# CH32V002F4P.net
KiCad netlist of a schematic drawn in Altium Designer
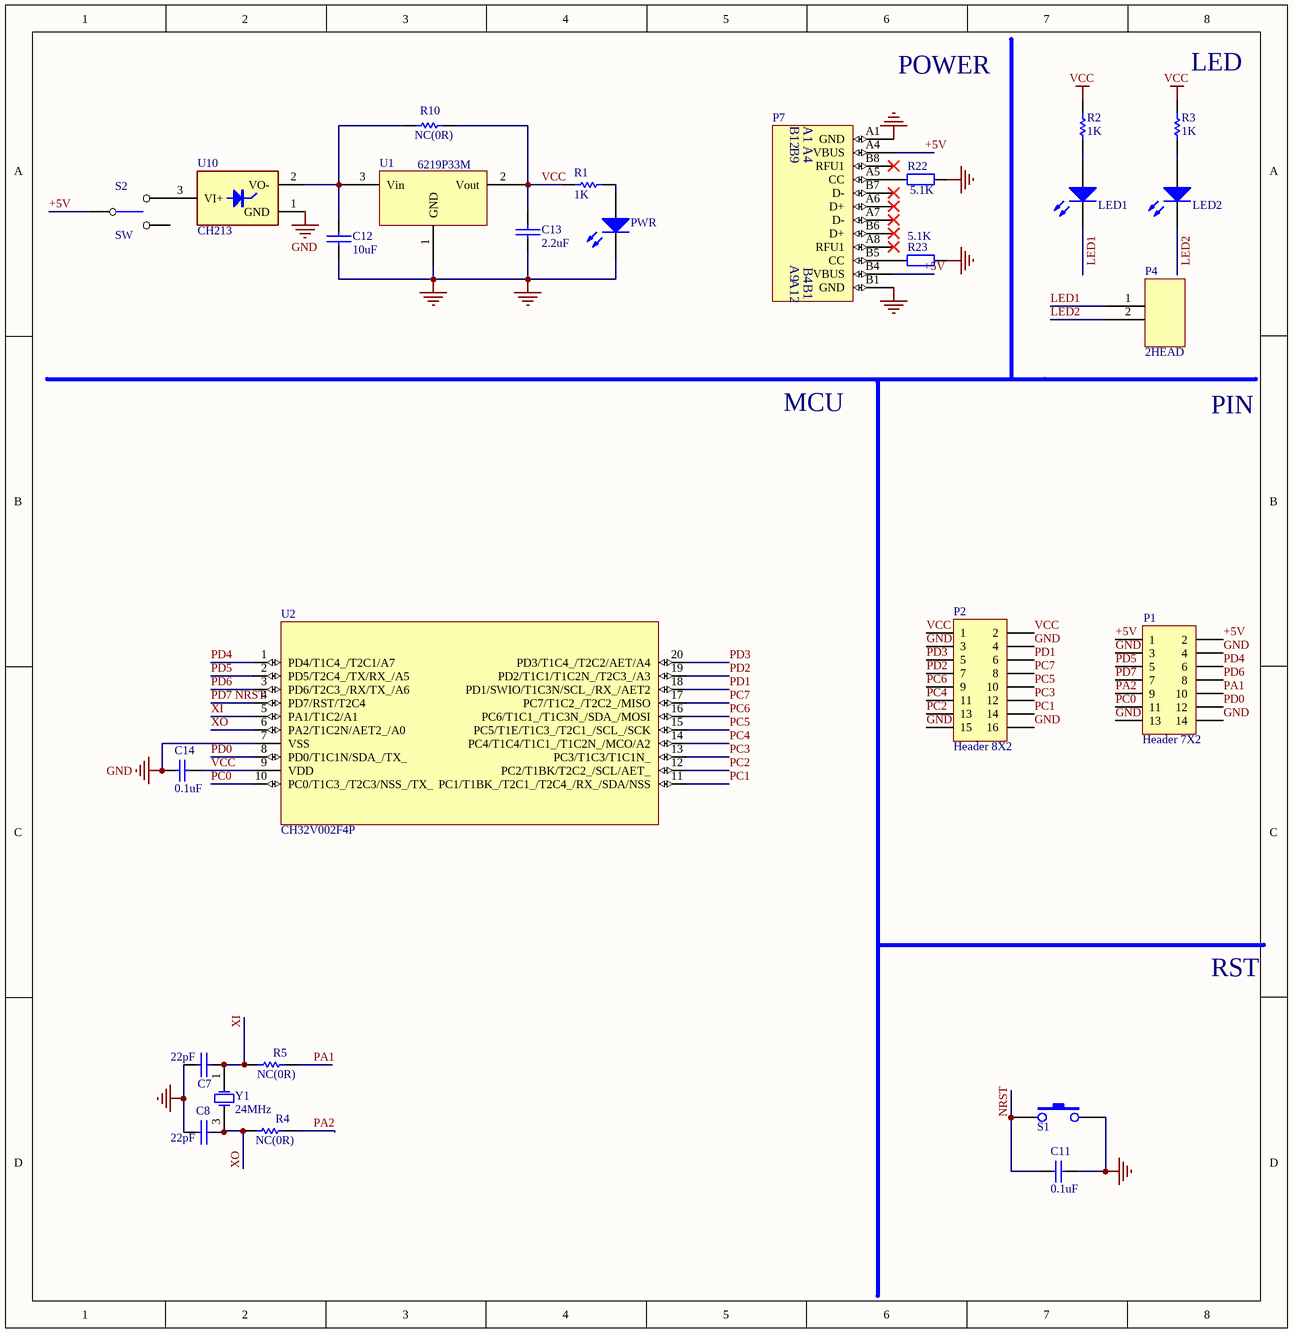
[diagram p0: CH32V002F4P.SchDoc]

(export (version "E")
  (design (tool "Eeschema 10.0.6"))
  (components
    (comp (ref "C7")
      (value "22pF")
      (footprint "0402_C")
      (description "Capacitor")
      (libsource (lib "*") (part "CAP"))
    )
    (comp (ref "C8")
      (value "22pF")
      (footprint "0402_C")
      (description "Capacitor")
      (libsource (lib "*") (part "CAP"))
    )
    (comp (ref "C11")
      (value "0.1uF")
      (footprint "0402_C")
      (description "Capacitor")
      (fields (field (name "PUBLISHER") "Altium Limited"))
      (libsource (lib "*") (part "Cap"))
    )
    (comp (ref "C12")
      (value "10uF")
      (footprint "0603_C")
      (description "Capacitor")
      (libsource (lib "wch_sch_others") (part "CAP"))
    )
    (comp (ref "C13")
      (value "2.2uF")
      (footprint "0402_C")
      (description "Capacitor")
      (libsource (lib "wch_sch_others") (part "CAP"))
    )
    (comp (ref "C14")
      (value "0.1uF")
      (footprint "0603_C")
      (description "Capacitor")
      (fields (field (name "PUBLISHER") "Altium Limited"))
      (libsource (lib "*") (part "Cap"))
    )
    (comp (ref "LED1")
      (value "LED1   blue")
      (footprint "0603+")
      (description "Typical INFRARED GaAs LED")
      (fields (field (name "PUBLISHER") "Altium Limited"))
      (libsource (lib "*") (part "LED0"))
    )
    (comp (ref "LED2")
      (value "LED2  blue")
      (footprint "0603+")
      (description "Typical INFRARED GaAs LED")
      (fields (field (name "PUBLISHER") "Altium Limited"))
      (libsource (lib "*") (part "LED0"))
    )
    (comp (ref "P1")
      (value "Header 7X2")
      (footprint "HDR2X7")
      (description "Header, 7-Pin, Dual row")
      (fields (field (name "PUBLISHER") "Altium Limited"))
      (libsource (lib "Miscellaneous Connectors") (part "Header 7X2"))
    )
    (comp (ref "P2")
      (value "Header 8X2")
      (footprint "HDR2X8")
      (description "Header, 8-Pin, Dual row")
      (fields (field (name "PUBLISHER") "Altium Limited"))
      (libsource (lib "Miscellaneous Connectors") (part "Header 8X2"))
    )
    (comp (ref "P4") (value "2HEAD") (footprint "SIP2-2.54mm") (libsource (lib "*") (part "2HEAD")))
    (comp (ref "P7")
      (value "TYPE-C")
      (footprint "TYPE-C-Receptacle-2.0")
      (libsource (lib "*") (part "TYPE-C1"))
    )
    (comp (ref "PWR")
      (value "POWER  red")
      (footprint "0603+")
      (description "Typical INFRARED GaAs LED")
      (fields (field (name "PUBLISHER") "Altium Limited"))
      (libsource (lib "") (part "LED0_1"))
    )
    (comp (ref "R1")
      (value "1K")
      (footprint "0402")
      (description "Semiconductor Resistor")
      (fields (field (name "PUBLISHER") "Altium Limited"))
      (libsource (lib "*") (part "Res Semi"))
    )
    (comp (ref "R2")
      (value "1K")
      (footprint "0402")
      (description "Semiconductor Resistor")
      (fields (field (name "PUBLISHER") "Altium Limited"))
      (libsource (lib "*") (part "Res Semi"))
    )
    (comp (ref "R3")
      (value "1K")
      (footprint "0402")
      (description "Semiconductor Resistor")
      (fields (field (name "PUBLISHER") "Altium Limited"))
      (libsource (lib "*") (part "Res Semi"))
    )
    (comp (ref "R4")
      (value "NC(0R)")
      (footprint "0402")
      (description "Semiconductor Resistor")
      (fields (field (name "Comment") "0R") (field (name "PUBLISHER") "Altium Limited"))
      (libsource (lib "*") (part "Res Semi"))
    )
    (comp (ref "R5")
      (value "NC(0R)")
      (footprint "0402")
      (description "Semiconductor Resistor")
      (fields (field (name "Comment") "0R") (field (name "PUBLISHER") "Altium Limited"))
      (libsource (lib "*") (part "Res Semi"))
    )
    (comp (ref "R10")
      (value "NC(0R)")
      (footprint "0402")
      (description "Semiconductor Resistor")
      (fields (field (name "Comment") "0R") (field (name "PUBLISHER") "Altium Limited"))
      (libsource (lib "*") (part "Res Semi"))
    )
    (comp (ref "R22")
      (value "5.1K")
      (footprint "0402")
      (description "Resistor")
      (libsource (lib "Miscellaneous Devices") (part "Res2"))
    )
    (comp (ref "R23")
      (value "5.1K")
      (footprint "0402")
      (description "Resistor")
      (libsource (lib "Miscellaneous Devices") (part "Res2"))
    )
    (comp (ref "S1") (value "NRST") (footprint "SMD_6.1x3.65x2.5mm-KEY") (libsource (lib "*") (part "KEY")))
    (comp (ref "S2") (value "SW") (footprint "SW1") (libsource (lib "*") (part "SW")))
    (comp (ref "U1")
      (value "6219P33M")
      (footprint "SOT-23")
      (libsource (lib "wch_sch_others") (part "6219P33M"))
    )
    (comp (ref "U2")
      (value "CH32V002F4P")
      (footprint "TSSOP20")
      (description "RISC-V MCU, 48MHz, ADC/UART/I2C/SPI")
      (libsource (lib "DHXXXSCH") (part "CH32V002F4P6"))
    )
    (comp (ref "U10")
      (value "CH213")
      (footprint "SOT-23-3")
      (description "Ideal Diode 5V*1A")
      (libsource (lib "CHXXX") (part "CH213E"))
    )
    (comp (ref "Y1")
      (value "24MHz")
      (footprint "XT3225")
      (description "Crystal Oscillator")
      (fields (field (name "PUBLISHER") "Altium Limited"))
      (libsource (lib "*") (part "XTAL"))
    )
  )
  (nets
    (net (code "1") (name "/+5V") (class "Default")
      (node (ref "P1") (pin "1") (pinfunction "1_1") (pintype "passive"))
      (node (ref "P1") (pin "2") (pinfunction "2_2") (pintype "passive"))
      (node (ref "P7") (pin "A4") (pinfunction "VBUS_A4") (pintype "bidirectional"))
      (node (ref "P7") (pin "B4") (pinfunction "VBUS_B4") (pintype "bidirectional"))
      (node (ref "S2") (pin "1") (pinfunction "1_1") (pintype "passive"))
    )
    (net (code "2") (name "/LED1") (class "Default")
      (node (ref "LED1") (pin "2") (pinfunction "K_2") (pintype "passive"))
      (node (ref "P4") (pin "1") (pintype "passive"))
    )
    (net (code "3") (name "/LED2") (class "Default")
      (node (ref "LED2") (pin "2") (pinfunction "K_2") (pintype "passive"))
      (node (ref "P4") (pin "2") (pintype "passive"))
    )
    (net (code "4") (name "/NRST") (class "Default")
      (node (ref "C11") (pin "2") (pinfunction "2_2") (pintype "passive"))
      (node (ref "P1") (pin "7") (pinfunction "7_7") (pintype "passive"))
      (node (ref "S1") (pin "1") (pinfunction "1_1") (pintype "passive"))
      (node (ref "U2") (pin "4") (pinfunction "PD7/RST/T2C4_4") (pintype "bidirectional"))
    )
    (net (code "5") (name "/PA1") (class "Default")
      (node (ref "P1") (pin "10") (pinfunction "10_10") (pintype "passive"))
      (node (ref "R5") (pin "2") (pinfunction "2_2") (pintype "passive"))
    )
    (net (code "6") (name "/PA2") (class "Default")
      (node (ref "P1") (pin "9") (pinfunction "9_9") (pintype "passive"))
      (node (ref "R4") (pin "2") (pinfunction "2_2") (pintype "passive"))
    )
    (net (code "7") (name "/PC0") (class "Default")
      (node (ref "P1") (pin "11") (pinfunction "11_11") (pintype "passive"))
      (node (ref "U2") (pin "10") (pinfunction "PC0/T1C3_/T2C3/NSS_/TX__10") (pintype "bidirectional"))
    )
    (net (code "8") (name "/PC1") (class "Default")
      (node (ref "P2") (pin "14") (pinfunction "14_14") (pintype "passive"))
      (node (ref "U2") (pin "11") (pinfunction "PC1/T1BK_/T2C1_/T2C4_/RX_/SDA/NSS_11") (pintype "bidirectional"))
    )
    (net (code "9") (name "/PC2") (class "Default")
      (node (ref "P2") (pin "13") (pinfunction "13_13") (pintype "passive"))
      (node (ref "U2") (pin "12") (pinfunction "PC2/T1BK/T2C2_/SCL/AET__12") (pintype "bidirectional"))
    )
    (net (code "10") (name "/PC3") (class "Default")
      (node (ref "P2") (pin "12") (pinfunction "12_12") (pintype "passive"))
      (node (ref "U2") (pin "13") (pinfunction "PC3/T1C3/T1C1N__13") (pintype "bidirectional"))
    )
    (net (code "11") (name "/PC4") (class "Default")
      (node (ref "P2") (pin "11") (pinfunction "11_11") (pintype "passive"))
      (node (ref "U2") (pin "14") (pinfunction "PC4/T1C4/T1C1_/T1C2N_/MCO/A2_14") (pintype "bidirectional"))
    )
    (net (code "12") (name "/PC5") (class "Default")
      (node (ref "P2") (pin "10") (pinfunction "10_10") (pintype "passive"))
      (node (ref "U2") (pin "15") (pinfunction "PC5/T1E/T1C3_/T2C1_/SCL_/SCK_15") (pintype "bidirectional"))
    )
    (net (code "13") (name "/PC6") (class "Default")
      (node (ref "P2") (pin "9") (pinfunction "9_9") (pintype "passive"))
      (node (ref "U2") (pin "16") (pinfunction "PC6/T1C1_/T1C3N_/SDA_/MOSI_16") (pintype "bidirectional"))
    )
    (net (code "14") (name "/PC7") (class "Default")
      (node (ref "P2") (pin "8") (pinfunction "8_8") (pintype "passive"))
      (node (ref "U2") (pin "17") (pinfunction "PC7/T1C2_/T2C2_/MISO_17") (pintype "bidirectional"))
    )
    (net (code "15") (name "/PD0") (class "Default")
      (node (ref "P1") (pin "12") (pinfunction "12_12") (pintype "passive"))
      (node (ref "U2") (pin "8") (pinfunction "PD0/T1C1N/SDA_/TX__8") (pintype "bidirectional"))
    )
    (net (code "16") (name "/PD1") (class "Default")
      (node (ref "P2") (pin "6") (pinfunction "6_6") (pintype "passive"))
      (node (ref "U2") (pin "18") (pinfunction "PD1/SWIO/T1C3N/SCL_/RX_/AET2_18") (pintype "bidirectional"))
    )
    (net (code "17") (name "/PD2") (class "Default")
      (node (ref "P2") (pin "7") (pinfunction "7_7") (pintype "passive"))
      (node (ref "U2") (pin "19") (pinfunction "PD2/T1C1/T1C2N_/T2C3_/A3_19") (pintype "bidirectional"))
    )
    (net (code "18") (name "/PD3") (class "Default")
      (node (ref "P2") (pin "5") (pinfunction "5_5") (pintype "passive"))
      (node (ref "U2") (pin "20") (pinfunction "PD3/T1C4_/T2C2/AET/A4_20") (pintype "bidirectional"))
    )
    (net (code "19") (name "/PD4") (class "Default")
      (node (ref "P1") (pin "6") (pinfunction "6_6") (pintype "passive"))
      (node (ref "U2") (pin "1") (pinfunction "PD4/T1C4_/T2C1/A7_1") (pintype "bidirectional"))
    )
    (net (code "20") (name "/PD5") (class "Default")
      (node (ref "P1") (pin "5") (pinfunction "5_5") (pintype "passive"))
      (node (ref "U2") (pin "2") (pinfunction "PD5/T2C4_/TX/RX_/A5_2") (pintype "bidirectional"))
    )
    (net (code "21") (name "/PD6") (class "Default")
      (node (ref "P1") (pin "8") (pinfunction "8_8") (pintype "passive"))
      (node (ref "U2") (pin "3") (pinfunction "PD6/T2C3_/RX/TX_/A6_3") (pintype "bidirectional"))
    )
    (net (code "22") (name "/XI") (class "Default")
      (node (ref "C7") (pin "2") (pinfunction "2_2") (pintype "passive"))
      (node (ref "R5") (pin "1") (pinfunction "1_1") (pintype "passive"))
      (node (ref "U2") (pin "5") (pinfunction "PA1/T1C2/A1_5") (pintype "bidirectional"))
      (node (ref "Y1") (pin "1") (pinfunction "OSC1_1") (pintype "passive"))
    )
    (net (code "23") (name "/XO") (class "Default")
      (node (ref "C8") (pin "2") (pinfunction "2_2") (pintype "passive"))
      (node (ref "R4") (pin "1") (pinfunction "1_1") (pintype "passive"))
      (node (ref "U2") (pin "6") (pinfunction "PA2/T1C2N/AET2_/A0_6") (pintype "bidirectional"))
      (node (ref "Y1") (pin "3") (pinfunction "OSC2_3") (pintype "passive"))
    )
    (net (code "24") (name "GND") (class "Default")
      (node (ref "C11") (pin "1") (pinfunction "1_1") (pintype "passive"))
      (node (ref "C12") (pin "2") (pinfunction "2_2") (pintype "passive"))
      (node (ref "C13") (pin "1") (pinfunction "1_1") (pintype "passive"))
      (node (ref "C14") (pin "2") (pinfunction "2_2") (pintype "passive"))
      (node (ref "C7") (pin "1") (pinfunction "1_1") (pintype "passive"))
      (node (ref "C8") (pin "1") (pinfunction "1_1") (pintype "passive"))
      (node (ref "P1") (pin "13") (pinfunction "13_13") (pintype "passive"))
      (node (ref "P1") (pin "14") (pinfunction "14_14") (pintype "passive"))
      (node (ref "P1") (pin "3") (pinfunction "3_3") (pintype "passive"))
      (node (ref "P1") (pin "4") (pinfunction "4_4") (pintype "passive"))
      (node (ref "P2") (pin "15") (pinfunction "15_15") (pintype "passive"))
      (node (ref "P2") (pin "16") (pinfunction "16_16") (pintype "passive"))
      (node (ref "P2") (pin "3") (pinfunction "3_3") (pintype "passive"))
      (node (ref "P2") (pin "4") (pinfunction "4_4") (pintype "passive"))
      (node (ref "P7") (pin "A1") (pinfunction "GND_A1") (pintype "bidirectional"))
      (node (ref "P7") (pin "B1") (pinfunction "GND_B1") (pintype "bidirectional"))
      (node (ref "PWR") (pin "2") (pinfunction "K_2") (pintype "passive"))
      (node (ref "R22") (pin "2") (pinfunction "2_2") (pintype "passive"))
      (node (ref "R23") (pin "2") (pinfunction "2_2") (pintype "passive"))
      (node (ref "S1") (pin "2") (pinfunction "2_2") (pintype "passive"))
      (node (ref "U1") (pin "1") (pinfunction "GND_1") (pintype "passive"))
      (node (ref "U10") (pin "1") (pinfunction "GND_1") (pintype "power_in"))
      (node (ref "U2") (pin "7") (pinfunction "VSS_7") (pintype "power_in"))
    )
    (net (code "25") (name "Net-(LED1-A)") (class "Default")
      (node (ref "LED1") (pin "1") (pinfunction "A_1") (pintype "passive"))
      (node (ref "R2") (pin "2") (pinfunction "2_2") (pintype "passive"))
    )
    (net (code "26") (name "Net-(LED2-A)") (class "Default")
      (node (ref "LED2") (pin "1") (pinfunction "A_1") (pintype "passive"))
      (node (ref "R3") (pin "2") (pinfunction "2_2") (pintype "passive"))
    )
    (net (code "27") (name "Net-(P7-CC-PadA5)") (class "Default")
      (node (ref "P7") (pin "A5") (pinfunction "CC_A5") (pintype "bidirectional"))
      (node (ref "R22") (pin "1") (pinfunction "1_1") (pintype "passive"))
    )
    (net (code "28") (name "Net-(P7-CC-PadB5)") (class "Default")
      (node (ref "P7") (pin "B5") (pinfunction "CC_B5") (pintype "bidirectional"))
      (node (ref "R23") (pin "1") (pinfunction "1_1") (pintype "passive"))
    )
    (net (code "29") (name "Net-(PWR-A)") (class "Default")
      (node (ref "PWR") (pin "1") (pinfunction "A_1") (pintype "passive"))
      (node (ref "R1") (pin "1") (pinfunction "1_1") (pintype "passive"))
    )
    (net (code "30") (name "Net-(U1-Vin)") (class "Default")
      (node (ref "C12") (pin "1") (pinfunction "1_1") (pintype "passive"))
      (node (ref "R10") (pin "1") (pinfunction "1_1") (pintype "passive"))
      (node (ref "U1") (pin "3") (pinfunction "Vin_3") (pintype "passive"))
      (node (ref "U10") (pin "2") (pinfunction "VO-_2") (pintype "power_in"))
    )
    (net (code "31") (name "Net-(U10-VI+)") (class "Default")
      (node (ref "S2") (pin "3") (pinfunction "3_3") (pintype "passive"))
      (node (ref "U10") (pin "3") (pinfunction "VI+_3") (pintype "power_in"))
    )
    (net (code "32") (name "VCC") (class "Default")
      (node (ref "C13") (pin "2") (pinfunction "2_2") (pintype "passive"))
      (node (ref "C14") (pin "1") (pinfunction "1_1") (pintype "passive"))
      (node (ref "P2") (pin "1") (pinfunction "1_1") (pintype "passive"))
      (node (ref "P2") (pin "2") (pinfunction "2_2") (pintype "passive"))
      (node (ref "R1") (pin "2") (pinfunction "2_2") (pintype "passive"))
      (node (ref "R10") (pin "2") (pinfunction "2_2") (pintype "passive"))
      (node (ref "R2") (pin "1") (pinfunction "1_1") (pintype "passive"))
      (node (ref "R3") (pin "1") (pinfunction "1_1") (pintype "passive"))
      (node (ref "U1") (pin "2") (pinfunction "Vout_2") (pintype "passive"))
      (node (ref "U2") (pin "9") (pinfunction "VDD_9") (pintype "power_in"))
    )
    (net (code "33") (name "unconnected-(P7-D+-PadA6)") (class "Default")
      (node (ref "P7") (pin "A6") (pinfunction "D+_A6") (pintype "bidirectional+no_connect"))
    )
    (net (code "34") (name "unconnected-(P7-D+-PadB6)") (class "Default")
      (node (ref "P7") (pin "B6") (pinfunction "D+_B6") (pintype "bidirectional+no_connect"))
    )
    (net (code "35") (name "unconnected-(P7-D--PadA7)") (class "Default")
      (node (ref "P7") (pin "A7") (pinfunction "D-_A7") (pintype "bidirectional+no_connect"))
    )
    (net (code "36") (name "unconnected-(P7-D--PadB7)") (class "Default")
      (node (ref "P7") (pin "B7") (pinfunction "D-_B7") (pintype "bidirectional+no_connect"))
    )
    (net (code "37") (name "unconnected-(P7-RFU1-PadA8)") (class "Default")
      (node (ref "P7") (pin "A8") (pinfunction "RFU1_A8") (pintype "bidirectional+no_connect"))
    )
    (net (code "38") (name "unconnected-(P7-RFU1-PadB8)") (class "Default")
      (node (ref "P7") (pin "B8") (pinfunction "RFU1_B8") (pintype "bidirectional+no_connect"))
    )
    (net (code "39") (name "unconnected-(S2-Pad2)") (class "Default")
      (node (ref "S2") (pin "2") (pinfunction "2_2") (pintype "passive"))
    )
  )
)
